# IRre.net
KiCad netlist of a schematic drawn in EAGLE
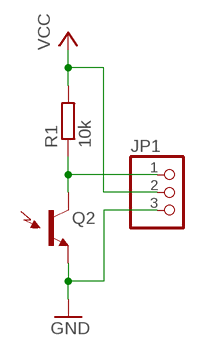
[diagram p0: schematic, sheet 1]

(export (version "E")
  (design (tool "Eeschema 10.0.6"))
  (components
    (comp (ref "JP1")
      (value "PINHD-1X3")
      (footprint "eagle-import:1X03")
      (libsource (lib "eagle-import") (part "PINHD-1X3"))
    )
    (comp (ref "Q2")
      (value "LTR-301")
      (footprint "eagle-import:LTR-301")
      (libsource (lib "eagle-import") (part "LTR-301"))
    )
    (comp (ref "R1")
      (value "10k")
      (footprint "eagle-import:R0805")
      (libsource (lib "eagle-import") (part "R-EU_R0805"))
    )
  )
  (nets
    (net (code "1") (name "GND") (class "Default")
      (node (ref "JP1") (pin "3") (pinfunction "3_3") (pintype "passive"))
      (node (ref "Q2") (pin "E") (pinfunction "E1_E") (pintype "passive"))
    )
    (net (code "2") (name "Net-(Q2-C1)") (class "Default")
      (node (ref "JP1") (pin "1") (pinfunction "1_1") (pintype "passive"))
      (node (ref "Q2") (pin "C") (pinfunction "C1_C") (pintype "passive"))
      (node (ref "R1") (pin "1") (pinfunction "1_1") (pintype "passive"))
    )
    (net (code "3") (name "VCC") (class "Default")
      (node (ref "JP1") (pin "2") (pinfunction "2_2") (pintype "passive"))
      (node (ref "R1") (pin "2") (pinfunction "2_2") (pintype "passive"))
    )
  )
)
